# Magician_encoder.net
KiCad netlist of a schematic drawn in EAGLE
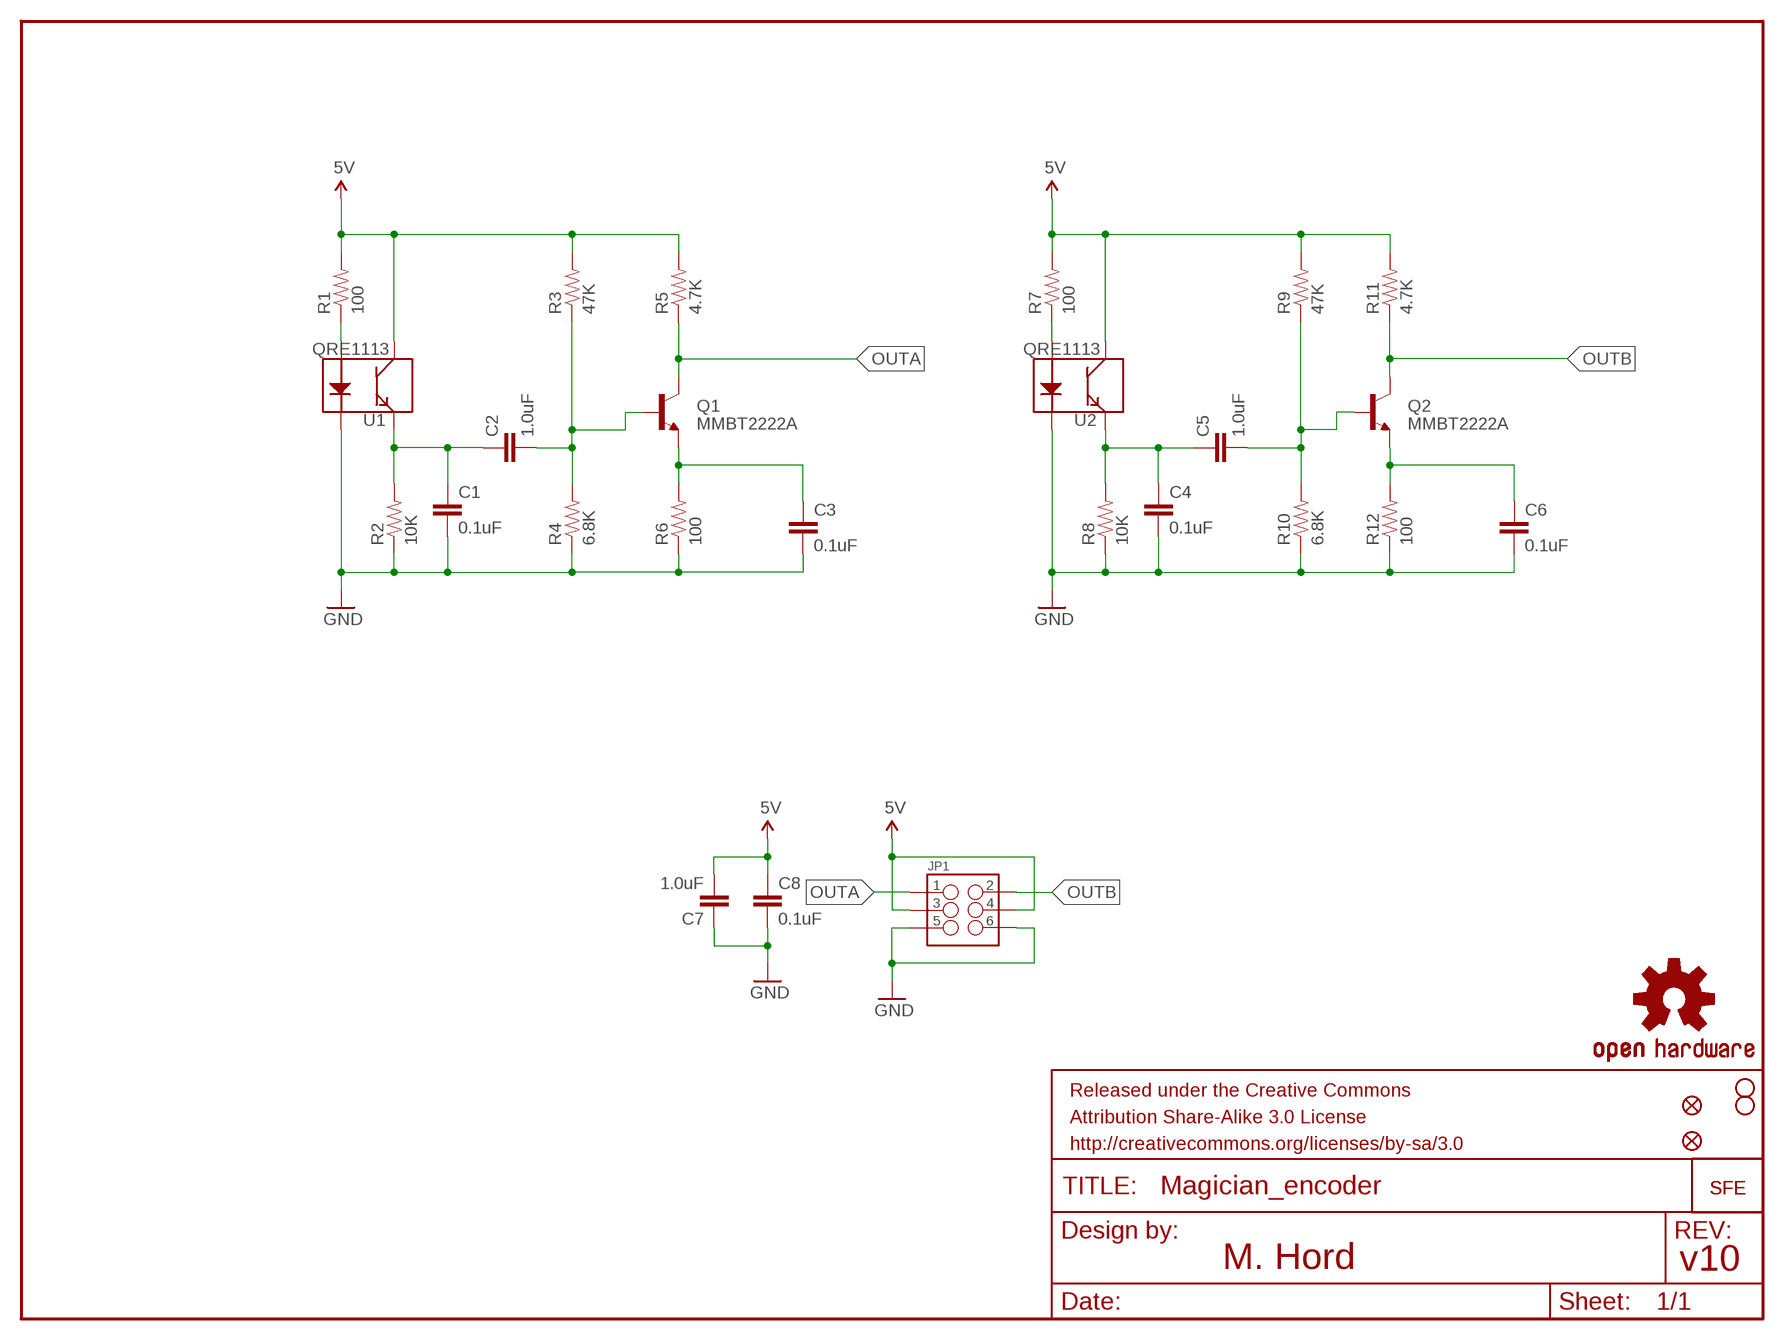
[diagram p0: schematic, sheet 1]

(export (version "E")
  (design (tool "Eeschema 10.0.6"))
  (components
    (comp (ref "C1")
      (value "0.1uF")
      (footprint "eagle-import:0603-CAP")
      (libsource (lib "eagle-import") (part "0.1UF-25V(+80/-20%)(0603)"))
    )
    (comp (ref "C2")
      (value "1.0uF")
      (footprint "eagle-import:0603-CAP")
      (libsource (lib "eagle-import") (part "1.0UF-16V-10%(0603)"))
    )
    (comp (ref "C3")
      (value "0.1uF")
      (footprint "eagle-import:0603-CAP")
      (libsource (lib "eagle-import") (part "0.1UF-25V(+80/-20%)(0603)"))
    )
    (comp (ref "C4")
      (value "0.1uF")
      (footprint "eagle-import:0603-CAP")
      (libsource (lib "eagle-import") (part "0.1UF-25V(+80/-20%)(0603)"))
    )
    (comp (ref "C5")
      (value "1.0uF")
      (footprint "eagle-import:0603-CAP")
      (libsource (lib "eagle-import") (part "1.0UF-16V-10%(0603)"))
    )
    (comp (ref "C6")
      (value "0.1uF")
      (footprint "eagle-import:0603-CAP")
      (libsource (lib "eagle-import") (part "0.1UF-25V(+80/-20%)(0603)"))
    )
    (comp (ref "C7")
      (value "1.0uF")
      (footprint "eagle-import:0603-CAP")
      (libsource (lib "eagle-import") (part "1.0UF-16V-10%(0603)"))
    )
    (comp (ref "C8")
      (value "0.1uF")
      (footprint "eagle-import:0603-CAP")
      (libsource (lib "eagle-import") (part "0.1UF-25V(+80/-20%)(0603)"))
    )
    (comp (ref "FID1")
      (value "FIDUCIALUFIDUCIAL")
      (footprint "eagle-import:MICRO-FIDUCIAL")
      (libsource (lib "eagle-import") (part "FIDUCIALUFIDUCIAL"))
    )
    (comp (ref "FID2")
      (value "FIDUCIALUFIDUCIAL")
      (footprint "eagle-import:MICRO-FIDUCIAL")
      (libsource (lib "eagle-import") (part "FIDUCIALUFIDUCIAL"))
    )
    (comp (ref "FRAME1")
      (value "FRAME-LETTER")
      (footprint "eagle-import:CREATIVE_COMMONS")
      (libsource (lib "eagle-import") (part "FRAME-LETTER"))
    )
    (comp (ref "JP1")
      (value "M03X22X3_SILK_SM")
      (footprint "eagle-import:2X3")
      (libsource (lib "eagle-import") (part "M03X22X3_SILK_SM"))
    )
    (comp (ref "LOGO1")
      (value "LOGO-SFESK")
      (footprint "eagle-import:SFE-LOGO-FLAME")
      (libsource (lib "eagle-import") (part "LOGO-SFESK"))
    )
    (comp (ref "LOGO3")
      (value "OSHW-LOGOS")
      (footprint "eagle-import:OSHW-LOGO-S")
      (libsource (lib "eagle-import") (part "OSHW-LOGOS"))
    )
    (comp (ref "LOGO4")
      (value "LOGO-SFENEW")
      (footprint "eagle-import:SFE-NEW-WEBLOGO")
      (libsource (lib "eagle-import") (part "LOGO-SFENEW"))
    )
    (comp (ref "Q1")
      (value "MMBT2222A")
      (footprint "eagle-import:SOT23")
      (libsource (lib "eagle-import") (part "TRANSISTOR_NPNMMBT2222A"))
    )
    (comp (ref "Q2")
      (value "MMBT2222A")
      (footprint "eagle-import:SOT23")
      (libsource (lib "eagle-import") (part "TRANSISTOR_NPNMMBT2222A"))
    )
    (comp (ref "R1")
      (value "100")
      (footprint "eagle-import:0603-RES")
      (libsource (lib "eagle-import") (part "100OHM1/10W1%(0603)"))
    )
    (comp (ref "R2")
      (value "10K")
      (footprint "eagle-import:0603-RES")
      (libsource (lib "eagle-import") (part "10KOHM1/10W1%(0603)0603"))
    )
    (comp (ref "R3")
      (value "47K")
      (footprint "eagle-import:0603-RES")
      (libsource (lib "eagle-import") (part "47KOHM1/10W1%(0603)"))
    )
    (comp (ref "R4")
      (value "6.8K")
      (footprint "eagle-import:0603-RES")
      (fields (field (name "PROD_ID") "RES-08597"))
      (libsource (lib "eagle-import") (part "10KOHM1/10W1%(0603)0603"))
    )
    (comp (ref "R5")
      (value "4.7K")
      (footprint "eagle-import:0603-RES")
      (fields (field (name "PROD_ID") "RES-07857"))
      (libsource (lib "eagle-import") (part "10KOHM1/10W1%(0603)0603"))
    )
    (comp (ref "R6")
      (value "100")
      (footprint "eagle-import:0603-RES")
      (fields (field (name "PROD_ID") "RES-07863"))
      (libsource (lib "eagle-import") (part "1KOHM1/10W1%(0603)"))
    )
    (comp (ref "R7")
      (value "100")
      (footprint "eagle-import:0603-RES")
      (libsource (lib "eagle-import") (part "100OHM1/10W1%(0603)"))
    )
    (comp (ref "R8")
      (value "10K")
      (footprint "eagle-import:0603-RES")
      (libsource (lib "eagle-import") (part "10KOHM1/10W1%(0603)0603"))
    )
    (comp (ref "R9")
      (value "47K")
      (footprint "eagle-import:0603-RES")
      (libsource (lib "eagle-import") (part "47KOHM1/10W1%(0603)"))
    )
    (comp (ref "R10")
      (value "6.8K")
      (footprint "eagle-import:0603-RES")
      (fields (field (name "PROD_ID") "RES-08597"))
      (libsource (lib "eagle-import") (part "10KOHM1/10W1%(0603)0603"))
    )
    (comp (ref "R11")
      (value "4.7K")
      (footprint "eagle-import:0603-RES")
      (fields (field (name "PROD_ID") "RES-07857"))
      (libsource (lib "eagle-import") (part "10KOHM1/10W1%(0603)0603"))
    )
    (comp (ref "R12")
      (value "100")
      (footprint "eagle-import:0603-RES")
      (fields (field (name "PROD_ID") "RES-07863"))
      (libsource (lib "eagle-import") (part "1KOHM1/10W1%(0603)"))
    )
    (comp (ref "STANDOFF1")
      (value "STAND-OFF")
      (footprint "eagle-import:STAND-OFF")
      (libsource (lib "eagle-import") (part "STAND-OFF"))
    )
    (comp (ref "STANDOFF2")
      (value "STAND-OFF")
      (footprint "eagle-import:STAND-OFF")
      (libsource (lib "eagle-import") (part "STAND-OFF"))
    )
    (comp (ref "U1")
      (value "QRE1113")
      (footprint "eagle-import:QRE1113")
      (libsource (lib "eagle-import") (part "QRE1113"))
    )
    (comp (ref "U2")
      (value "QRE1113")
      (footprint "eagle-import:QRE1113")
      (libsource (lib "eagle-import") (part "QRE1113"))
    )
  )
  (nets
    (net (code "1") (name "5V") (class "Default")
      (node (ref "C7") (pin "2") (pinfunction "2_2") (pintype "passive"))
      (node (ref "C8") (pin "1") (pinfunction "1_1") (pintype "passive"))
      (node (ref "JP1") (pin "3") (pinfunction "3_3") (pintype "bidirectional"))
      (node (ref "JP1") (pin "4") (pinfunction "4_4") (pintype "bidirectional"))
      (node (ref "R1") (pin "2") (pinfunction "2_2") (pintype "passive"))
      (node (ref "R11") (pin "2") (pinfunction "2_2") (pintype "passive"))
      (node (ref "R3") (pin "2") (pinfunction "2_2") (pintype "passive"))
      (node (ref "R5") (pin "2") (pinfunction "2_2") (pintype "passive"))
      (node (ref "R7") (pin "2") (pinfunction "2_2") (pintype "passive"))
      (node (ref "R9") (pin "2") (pinfunction "2_2") (pintype "passive"))
      (node (ref "U1") (pin "3") (pinfunction "C_3") (pintype "bidirectional"))
      (node (ref "U2") (pin "3") (pinfunction "C_3") (pintype "bidirectional"))
    )
    (net (code "2") (name "GND") (class "Default")
      (node (ref "C1") (pin "2") (pinfunction "2_2") (pintype "passive"))
      (node (ref "C3") (pin "2") (pinfunction "2_2") (pintype "passive"))
      (node (ref "C4") (pin "2") (pinfunction "2_2") (pintype "passive"))
      (node (ref "C6") (pin "2") (pinfunction "2_2") (pintype "passive"))
      (node (ref "C7") (pin "1") (pinfunction "1_1") (pintype "passive"))
      (node (ref "C8") (pin "2") (pinfunction "2_2") (pintype "passive"))
      (node (ref "JP1") (pin "5") (pinfunction "5_5") (pintype "bidirectional"))
      (node (ref "JP1") (pin "6") (pinfunction "6_6") (pintype "bidirectional"))
      (node (ref "R10") (pin "1") (pinfunction "1_1") (pintype "passive"))
      (node (ref "R12") (pin "1") (pinfunction "1_1") (pintype "passive"))
      (node (ref "R2") (pin "1") (pinfunction "1_1") (pintype "passive"))
      (node (ref "R4") (pin "1") (pinfunction "1_1") (pintype "passive"))
      (node (ref "R6") (pin "1") (pinfunction "1_1") (pintype "passive"))
      (node (ref "R8") (pin "1") (pinfunction "1_1") (pintype "passive"))
      (node (ref "U1") (pin "2") (pinfunction "K_2") (pintype "bidirectional"))
      (node (ref "U2") (pin "2") (pinfunction "K_2") (pintype "bidirectional"))
    )
    (net (code "3") (name "Net-(Q1-B)") (class "Default")
      (node (ref "C2") (pin "2") (pinfunction "2_2") (pintype "passive"))
      (node (ref "Q1") (pin "1") (pinfunction "B_1") (pintype "passive"))
      (node (ref "R3") (pin "1") (pinfunction "1_1") (pintype "passive"))
      (node (ref "R4") (pin "2") (pinfunction "2_2") (pintype "passive"))
    )
    (net (code "4") (name "Net-(Q1-E)") (class "Default")
      (node (ref "C3") (pin "1") (pinfunction "1_1") (pintype "passive"))
      (node (ref "Q1") (pin "2") (pinfunction "E_2") (pintype "passive"))
      (node (ref "R6") (pin "2") (pinfunction "2_2") (pintype "passive"))
    )
    (net (code "5") (name "Net-(Q2-B)") (class "Default")
      (node (ref "C5") (pin "2") (pinfunction "2_2") (pintype "passive"))
      (node (ref "Q2") (pin "1") (pinfunction "B_1") (pintype "passive"))
      (node (ref "R10") (pin "2") (pinfunction "2_2") (pintype "passive"))
      (node (ref "R9") (pin "1") (pinfunction "1_1") (pintype "passive"))
    )
    (net (code "6") (name "Net-(Q2-E)") (class "Default")
      (node (ref "C6") (pin "1") (pinfunction "1_1") (pintype "passive"))
      (node (ref "Q2") (pin "2") (pinfunction "E_2") (pintype "passive"))
      (node (ref "R12") (pin "2") (pinfunction "2_2") (pintype "passive"))
    )
    (net (code "7") (name "Net-(U1-A)") (class "Default")
      (node (ref "R1") (pin "1") (pinfunction "1_1") (pintype "passive"))
      (node (ref "U1") (pin "1") (pinfunction "A_1") (pintype "bidirectional"))
    )
    (net (code "8") (name "Net-(U1-E)") (class "Default")
      (node (ref "C1") (pin "1") (pinfunction "1_1") (pintype "passive"))
      (node (ref "C2") (pin "1") (pinfunction "1_1") (pintype "passive"))
      (node (ref "R2") (pin "2") (pinfunction "2_2") (pintype "passive"))
      (node (ref "U1") (pin "4") (pinfunction "E_4") (pintype "bidirectional"))
    )
    (net (code "9") (name "Net-(U2-A)") (class "Default")
      (node (ref "R7") (pin "1") (pinfunction "1_1") (pintype "passive"))
      (node (ref "U2") (pin "1") (pinfunction "A_1") (pintype "bidirectional"))
    )
    (net (code "10") (name "Net-(U2-E)") (class "Default")
      (node (ref "C4") (pin "1") (pinfunction "1_1") (pintype "passive"))
      (node (ref "C5") (pin "1") (pinfunction "1_1") (pintype "passive"))
      (node (ref "R8") (pin "2") (pinfunction "2_2") (pintype "passive"))
      (node (ref "U2") (pin "4") (pinfunction "E_4") (pintype "bidirectional"))
    )
    (net (code "11") (name "OUTA") (class "Default")
      (node (ref "JP1") (pin "1") (pinfunction "1_1") (pintype "bidirectional"))
      (node (ref "Q1") (pin "3") (pinfunction "C_3") (pintype "passive"))
      (node (ref "R5") (pin "1") (pinfunction "1_1") (pintype "passive"))
    )
    (net (code "12") (name "OUTB") (class "Default")
      (node (ref "JP1") (pin "2") (pinfunction "2_2") (pintype "bidirectional"))
      (node (ref "Q2") (pin "3") (pinfunction "C_3") (pintype "passive"))
      (node (ref "R11") (pin "1") (pinfunction "1_1") (pintype "passive"))
    )
  )
)
